# Power.net
KiCad netlist of a schematic drawn in Altium Designer
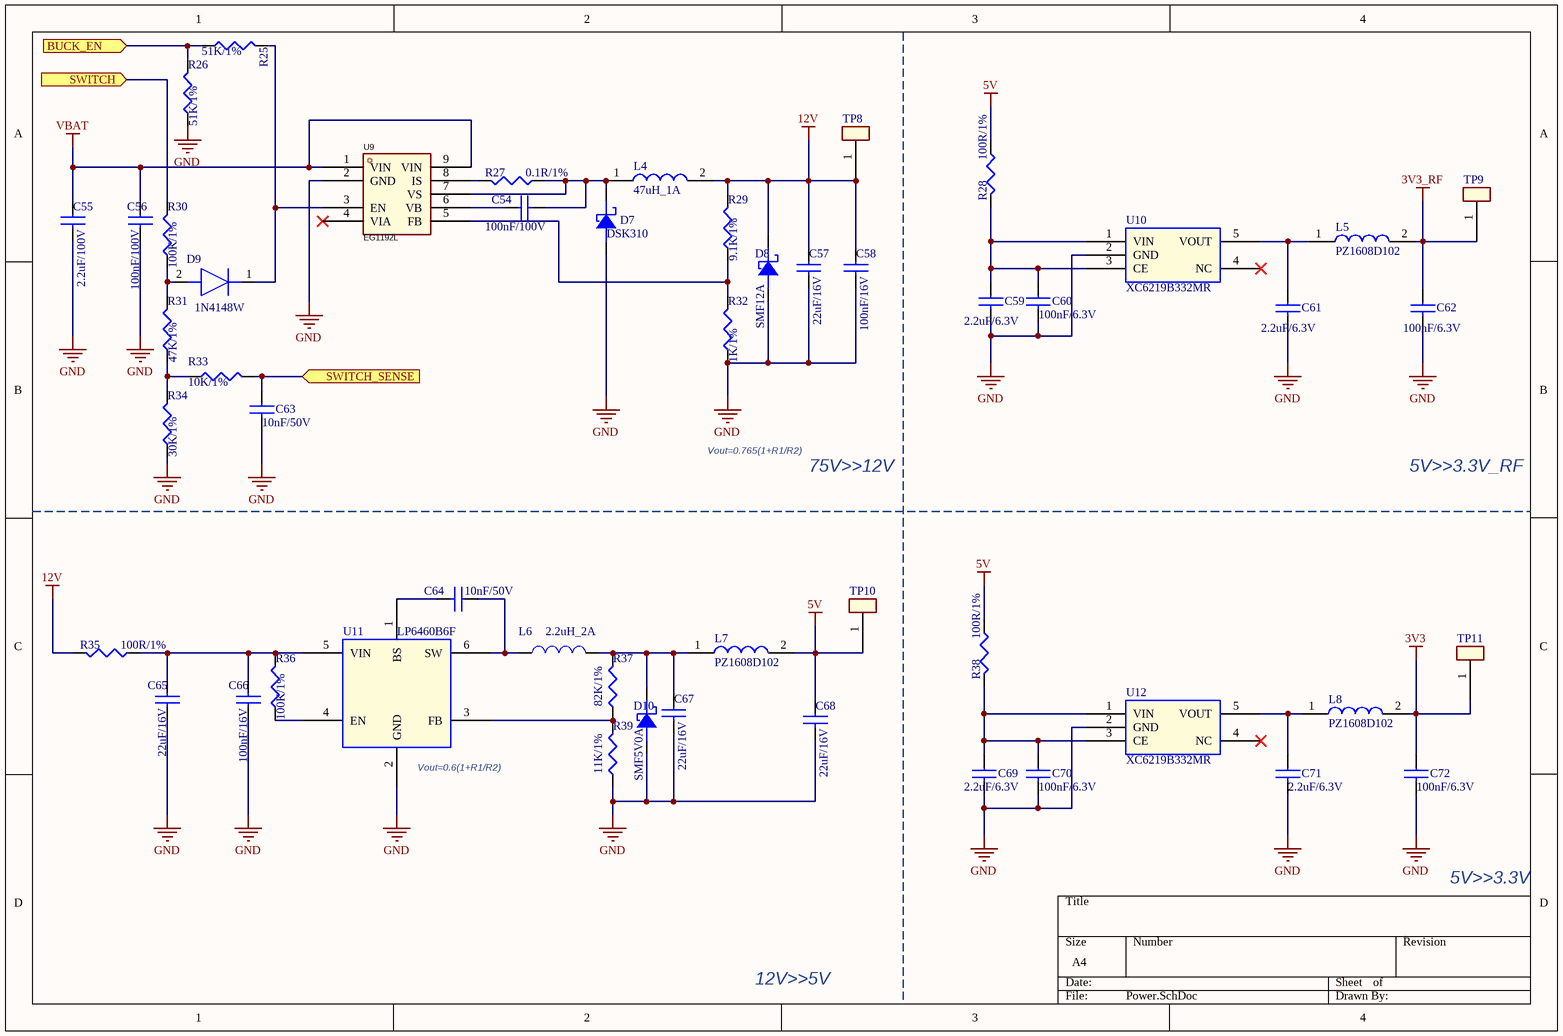
[diagram p0: Power.SchDoc]

(export (version "E")
  (design (tool "Eeschema 10.0.6"))
  (components
    (comp (ref "C54") (value "100nF/100V") (footprint "C0603") (libsource (lib "*") (part "CAP NP")))
    (comp (ref "C55") (value "2.2uF/100V") (footprint "C1206") (libsource (lib "*") (part "CAP NP")))
    (comp (ref "C56") (value "100nF/100V") (footprint "C0603") (libsource (lib "*") (part "CAP NP")))
    (comp (ref "C57") (value "22uF/16V") (footprint "C0805") (libsource (lib "*") (part "CAP NP")))
    (comp (ref "C58") (value "100nF/16V") (footprint "C0805") (libsource (lib "*") (part "CAP NP")))
    (comp (ref "C59") (value "2.2uF/6.3V") (footprint "C0402") (libsource (lib "*") (part "CAP NP")))
    (comp (ref "C60") (value "100nF/6.3V") (footprint "C0402") (libsource (lib "*") (part "CAP NP")))
    (comp (ref "C61") (value "2.2uF/6.3V") (footprint "C0402") (libsource (lib "*") (part "CAP NP")))
    (comp (ref "C62") (value "100nF/6.3V") (footprint "C0402") (libsource (lib "*") (part "CAP NP")))
    (comp (ref "C63") (value "10nF/50V") (footprint "C0402") (libsource (lib "*") (part "CAP NP")))
    (comp (ref "C64") (value "10nF/50V") (footprint "C0402") (libsource (lib "*") (part "CAP NP")))
    (comp (ref "C65") (value "22uF/16V") (footprint "C0805") (libsource (lib "*") (part "CAP NP")))
    (comp (ref "C66") (value "100nF/16V") (footprint "C0805") (libsource (lib "*") (part "CAP NP")))
    (comp (ref "C67") (value "22uF/16V") (footprint "C0805") (libsource (lib "*") (part "CAP NP")))
    (comp (ref "C68") (value "22uF/16V") (footprint "C0805") (libsource (lib "*") (part "CAP NP")))
    (comp (ref "C69") (value "2.2uF/6.3V") (footprint "C0402") (libsource (lib "*") (part "CAP NP")))
    (comp (ref "C70") (value "100nF/6.3V") (footprint "C0402") (libsource (lib "*") (part "CAP NP")))
    (comp (ref "C71") (value "2.2uF/6.3V") (footprint "C0402") (libsource (lib "*") (part "CAP NP")))
    (comp (ref "C72") (value "100nF/6.3V") (footprint "C0402") (libsource (lib "*") (part "CAP NP")))
    (comp (ref "D7") (value "DSK310") (footprint "SOD-123F") (libsource (lib "*") (part "DIODE SCHOTTKY21")))
    (comp (ref "D8") (value "SMF12A") (footprint "SOD-123F") (libsource (lib "*") (part "DIODE SCHOTTKY21")))
    (comp (ref "D9")
      (value "1N4148W")
      (footprint "1N4148WVGS08")
      (description "Diode")
      (fields
        (field (name "MANUFACTURER_PART_NUMBER") "1N4148W-V-GS08")
        (field (name "MOUSER PART NUMBER") "625-1N4148W-V")
      )
      (libsource (lib "VESC_DEVICE_Library") (part "1N4148W-V-GS08"))
    )
    (comp (ref "D10")
      (value "SMF5V0A")
      (footprint "SOD-123F")
      (libsource (lib "*") (part "DIODE SCHOTTKY21"))
    )
    (comp (ref "L4")
      (value "47uH_1A")
      (footprint "L5040")
      (description "Inductor")
      (fields
        (field (name "MANUFACTURER_PART_NUMBER") "74404054221")
        (field (name "MOUSER PART NUMBER") "710-74404054221")
      )
      (libsource (lib "VESC_DEVICE_Library") (part "74404054221"))
    )
    (comp (ref "L5")
      (value "PZ1608D102")
      (footprint "L0603")
      (description "Inductor")
      (fields
        (field (name "MANUFACTURER_PART_NUMBER") "LQG15HS4N7C02D")
        (field (name "MOUSER PART NUMBER") "81-LQG15HS4N7C02D")
      )
      (libsource (lib "VESC_DEVICE_Library") (part "PZ1608D102"))
    )
    (comp (ref "L6") (value "2.2uH_2A") (footprint "L4020") (libsource (lib "*") (part "INDUCTOR")))
    (comp (ref "L7")
      (value "PZ1608D102")
      (footprint "L0603")
      (description "Inductor")
      (fields
        (field (name "MANUFACTURER_PART_NUMBER") "LQG15HS4N7C02D")
        (field (name "MOUSER PART NUMBER") "81-LQG15HS4N7C02D")
      )
      (libsource (lib "VESC_DEVICE_Library") (part "PZ1608D102"))
    )
    (comp (ref "L8")
      (value "PZ1608D102")
      (footprint "L0603")
      (description "Inductor")
      (fields
        (field (name "MANUFACTURER_PART_NUMBER") "LQG15HS4N7C02D")
        (field (name "MOUSER PART NUMBER") "81-LQG15HS4N7C02D")
      )
      (libsource (lib "VESC_DEVICE_Library") (part "PZ1608D102"))
    )
    (comp (ref "R25") (value "51K/1%") (footprint "R0402") (libsource (lib "*") (part "RESISTOR")))
    (comp (ref "R26") (value "51K/1%") (footprint "R0402") (libsource (lib "*") (part "RESISTOR")))
    (comp (ref "R27") (value "0.1R/1%") (footprint "R0603") (libsource (lib "*") (part "RESISTOR")))
    (comp (ref "R28") (value "100R/1%") (footprint "R0603") (libsource (lib "*") (part "RESISTOR")))
    (comp (ref "R29") (value "9.1K/1%") (footprint "R0402") (libsource (lib "*") (part "RESISTOR")))
    (comp (ref "R30") (value "100K/1%") (footprint "R0402") (libsource (lib "*") (part "RESISTOR")))
    (comp (ref "R31") (value "47K/1%") (footprint "R0402") (libsource (lib "*") (part "RESISTOR")))
    (comp (ref "R32") (value "1K/1%") (footprint "R0402") (libsource (lib "*") (part "RESISTOR")))
    (comp (ref "R33") (value "10K/1%") (footprint "R0402") (libsource (lib "*") (part "RESISTOR")))
    (comp (ref "R34") (value "30K/1%") (footprint "R0402") (libsource (lib "*") (part "RESISTOR")))
    (comp (ref "R35") (value "100R/1%") (footprint "R0603") (libsource (lib "*") (part "RESISTOR")))
    (comp (ref "R36") (value "100K/1%") (footprint "R0402") (libsource (lib "*") (part "RESISTOR")))
    (comp (ref "R37") (value "82K/1%") (footprint "R0402") (libsource (lib "*") (part "RESISTOR")))
    (comp (ref "R38") (value "100R/1%") (footprint "R0603") (libsource (lib "*") (part "RESISTOR")))
    (comp (ref "R39") (value "11K/1%") (footprint "R0402") (libsource (lib "*") (part "RESISTOR")))
    (comp (ref "TP8")
      (value "TEST POINT")
      (footprint "test_point_100_smd")
      (libsource (lib "VESC_DEVICE_Library") (part "TEST POINT"))
    )
    (comp (ref "TP9")
      (value "TEST POINT")
      (footprint "test_point_100_smd")
      (libsource (lib "VESC_DEVICE_Library") (part "TEST POINT"))
    )
    (comp (ref "TP10")
      (value "TEST POINT")
      (footprint "test_point_100_smd")
      (libsource (lib "VESC_DEVICE_Library") (part "TEST POINT"))
    )
    (comp (ref "TP11")
      (value "TEST POINT")
      (footprint "test_point_100_smd")
      (libsource (lib "VESC_DEVICE_Library") (part "TEST POINT"))
    )
    (comp (ref "U9")
      (value "EG1192L")
      (footprint "ESOP-8_L4.9-W3.9-P1.27-LS6.0-BL-EP-1")
      (fields (field (name "MANUFACTURER") "EG(屹晶微)") (field (name "MANUFACTURER PART") "EG1198"))
      (libsource (lib "VESC_DEVICE_Library") (part "EG1192L"))
    )
    (comp (ref "U10")
      (value "XC6219B332MR")
      (footprint "SOT-23-5")
      (libsource (lib "*") (part "XC6219B332MR"))
    )
    (comp (ref "U11") (value "LP6460B6F") (footprint "SOT-23-6") (libsource (lib "*") (part "LP6460B6F")))
    (comp (ref "U12")
      (value "XC6219B332MR")
      (footprint "SOT-23-5")
      (libsource (lib "*") (part "XC6219B332MR"))
    )
  )
  (nets
    (net (code "1") (name "/BUCK_EN") (class "Default")
      (node (ref "R25") (pin "1") (pinfunction "1_1") (pintype "passive"))
      (node (ref "R26") (pin "2") (pinfunction "2_2") (pintype "passive"))
    )
    (net (code "2") (name "/SWITCH") (class "Default")
      (node (ref "R30") (pin "2") (pinfunction "2_2") (pintype "passive"))
    )
    (net (code "3") (name "/SWITCH_SENSE") (class "Default")
      (node (ref "C63") (pin "1") (pinfunction "1_1") (pintype "passive"))
      (node (ref "R33") (pin "2") (pinfunction "2_2") (pintype "passive"))
    )
    (net (code "4") (name "3V3") (class "Default")
      (node (ref "C72") (pin "1") (pinfunction "1_1") (pintype "passive"))
      (node (ref "L8") (pin "2") (pinfunction "2_2") (pintype "passive"))
      (node (ref "TP11") (pin "1") (pinfunction "1_1") (pintype "passive"))
    )
    (net (code "5") (name "3V3_RF") (class "Default")
      (node (ref "C62") (pin "1") (pinfunction "1_1") (pintype "passive"))
      (node (ref "L5") (pin "2") (pinfunction "2_2") (pintype "passive"))
      (node (ref "TP9") (pin "1") (pinfunction "1_1") (pintype "passive"))
    )
    (net (code "6") (name "5V") (class "Default")
      (node (ref "C68") (pin "1") (pinfunction "1_1") (pintype "passive"))
      (node (ref "L7") (pin "2") (pinfunction "2_2") (pintype "passive"))
      (node (ref "R28") (pin "1") (pinfunction "1_1") (pintype "passive"))
      (node (ref "R38") (pin "1") (pinfunction "1_1") (pintype "passive"))
      (node (ref "TP10") (pin "1") (pinfunction "1_1") (pintype "passive"))
    )
    (net (code "7") (name "12V") (class "Default")
      (node (ref "C57") (pin "1") (pinfunction "1_1") (pintype "passive"))
      (node (ref "C58") (pin "1") (pinfunction "1_1") (pintype "passive"))
      (node (ref "D8") (pin "1") (pinfunction "K_1") (pintype "passive"))
      (node (ref "L4") (pin "2") (pinfunction "2_2") (pintype "passive"))
      (node (ref "R29") (pin "2") (pinfunction "2_2") (pintype "passive"))
      (node (ref "R35") (pin "2") (pinfunction "2_2") (pintype "passive"))
      (node (ref "TP8") (pin "1") (pinfunction "1_1") (pintype "passive"))
    )
    (net (code "8") (name "GND") (class "Default")
      (node (ref "C55") (pin "2") (pinfunction "2_2") (pintype "passive"))
      (node (ref "C56") (pin "2") (pinfunction "2_2") (pintype "passive"))
      (node (ref "C57") (pin "2") (pinfunction "2_2") (pintype "passive"))
      (node (ref "C58") (pin "2") (pinfunction "2_2") (pintype "passive"))
      (node (ref "C59") (pin "2") (pinfunction "2_2") (pintype "passive"))
      (node (ref "C60") (pin "2") (pinfunction "2_2") (pintype "passive"))
      (node (ref "C61") (pin "2") (pinfunction "2_2") (pintype "passive"))
      (node (ref "C62") (pin "2") (pinfunction "2_2") (pintype "passive"))
      (node (ref "C63") (pin "2") (pinfunction "2_2") (pintype "passive"))
      (node (ref "C65") (pin "2") (pinfunction "2_2") (pintype "passive"))
      (node (ref "C66") (pin "2") (pinfunction "2_2") (pintype "passive"))
      (node (ref "C67") (pin "2") (pinfunction "2_2") (pintype "passive"))
      (node (ref "C68") (pin "2") (pinfunction "2_2") (pintype "passive"))
      (node (ref "C69") (pin "2") (pinfunction "2_2") (pintype "passive"))
      (node (ref "C70") (pin "2") (pinfunction "2_2") (pintype "passive"))
      (node (ref "C71") (pin "2") (pinfunction "2_2") (pintype "passive"))
      (node (ref "C72") (pin "2") (pinfunction "2_2") (pintype "passive"))
      (node (ref "D10") (pin "2") (pinfunction "A_2") (pintype "passive"))
      (node (ref "D7") (pin "2") (pinfunction "A_2") (pintype "passive"))
      (node (ref "D8") (pin "2") (pinfunction "A_2") (pintype "passive"))
      (node (ref "R26") (pin "1") (pinfunction "1_1") (pintype "passive"))
      (node (ref "R32") (pin "1") (pinfunction "1_1") (pintype "passive"))
      (node (ref "R34") (pin "1") (pinfunction "1_1") (pintype "passive"))
      (node (ref "R39") (pin "1") (pinfunction "1_1") (pintype "passive"))
      (node (ref "U10") (pin "2") (pinfunction "GND_2") (pintype "passive"))
      (node (ref "U11") (pin "2") (pinfunction "GND_2") (pintype "passive"))
      (node (ref "U12") (pin "2") (pinfunction "GND_2") (pintype "passive"))
      (node (ref "U9") (pin "2") (pinfunction "GND_2") (pintype "passive"))
    )
    (net (code "9") (name "Net-(D7-K)") (class "Default")
      (node (ref "C54") (pin "2") (pinfunction "2_2") (pintype "passive"))
      (node (ref "D7") (pin "1") (pinfunction "K_1") (pintype "passive"))
      (node (ref "L4") (pin "1") (pinfunction "1_1") (pintype "passive"))
      (node (ref "R27") (pin "1") (pinfunction "1_1") (pintype "passive"))
      (node (ref "U9") (pin "7") (pinfunction "VS_7") (pintype "passive"))
    )
    (net (code "10") (name "Net-(D9-A)") (class "Default")
      (node (ref "D9") (pin "2") (pinfunction "A_2") (pintype "passive"))
      (node (ref "R30") (pin "1") (pinfunction "1_1") (pintype "passive"))
      (node (ref "R31") (pin "2") (pinfunction "2_2") (pintype "passive"))
    )
    (net (code "11") (name "Net-(D9-K)") (class "Default")
      (node (ref "D9") (pin "1") (pinfunction "K_1") (pintype "passive"))
      (node (ref "R25") (pin "2") (pinfunction "2_2") (pintype "passive"))
      (node (ref "U9") (pin "3") (pinfunction "EN_3") (pintype "passive"))
    )
    (net (code "12") (name "Net-(D10-K)") (class "Default")
      (node (ref "C67") (pin "1") (pinfunction "1_1") (pintype "passive"))
      (node (ref "D10") (pin "1") (pinfunction "K_1") (pintype "passive"))
      (node (ref "L6") (pin "2") (pinfunction "2_2") (pintype "passive"))
      (node (ref "L7") (pin "1") (pinfunction "1_1") (pintype "passive"))
      (node (ref "R37") (pin "2") (pinfunction "2_2") (pintype "passive"))
    )
    (net (code "13") (name "Net-(R31-Pad1)") (class "Default")
      (node (ref "R31") (pin "1") (pinfunction "1_1") (pintype "passive"))
      (node (ref "R33") (pin "1") (pinfunction "1_1") (pintype "passive"))
      (node (ref "R34") (pin "2") (pinfunction "2_2") (pintype "passive"))
    )
    (net (code "14") (name "Net-(U9-FB)") (class "Default")
      (node (ref "R29") (pin "1") (pinfunction "1_1") (pintype "passive"))
      (node (ref "R32") (pin "2") (pinfunction "2_2") (pintype "passive"))
      (node (ref "U9") (pin "5") (pinfunction "FB_5") (pintype "passive"))
    )
    (net (code "15") (name "Net-(U9-IS)") (class "Default")
      (node (ref "R27") (pin "2") (pinfunction "2_2") (pintype "passive"))
      (node (ref "U9") (pin "8") (pinfunction "IS_8") (pintype "passive"))
    )
    (net (code "16") (name "Net-(U9-VB)") (class "Default")
      (node (ref "C54") (pin "1") (pinfunction "1_1") (pintype "passive"))
      (node (ref "U9") (pin "6") (pinfunction "VB_6") (pintype "passive"))
    )
    (net (code "17") (name "Net-(U10-CE)") (class "Default")
      (node (ref "C59") (pin "1") (pinfunction "1_1") (pintype "passive"))
      (node (ref "C60") (pin "1") (pinfunction "1_1") (pintype "passive"))
      (node (ref "R28") (pin "2") (pinfunction "2_2") (pintype "passive"))
      (node (ref "U10") (pin "1") (pinfunction "VIN_1") (pintype "passive"))
      (node (ref "U10") (pin "3") (pinfunction "CE_3") (pintype "passive"))
    )
    (net (code "18") (name "Net-(U10-VOUT)") (class "Default")
      (node (ref "C61") (pin "1") (pinfunction "1_1") (pintype "passive"))
      (node (ref "L5") (pin "1") (pinfunction "1_1") (pintype "passive"))
      (node (ref "U10") (pin "5") (pinfunction "VOUT_5") (pintype "passive"))
    )
    (net (code "19") (name "Net-(U11-BS)") (class "Default")
      (node (ref "C64") (pin "2") (pinfunction "2_2") (pintype "passive"))
      (node (ref "U11") (pin "1") (pinfunction "BS_1") (pintype "passive"))
    )
    (net (code "20") (name "Net-(U11-EN)") (class "Default")
      (node (ref "R36") (pin "1") (pinfunction "1_1") (pintype "passive"))
      (node (ref "U11") (pin "4") (pinfunction "EN_4") (pintype "passive"))
    )
    (net (code "21") (name "Net-(U11-FB)") (class "Default")
      (node (ref "R37") (pin "1") (pinfunction "1_1") (pintype "passive"))
      (node (ref "R39") (pin "2") (pinfunction "2_2") (pintype "passive"))
      (node (ref "U11") (pin "3") (pinfunction "FB_3") (pintype "passive"))
    )
    (net (code "22") (name "Net-(U11-SW)") (class "Default")
      (node (ref "C64") (pin "1") (pinfunction "1_1") (pintype "passive"))
      (node (ref "L6") (pin "1") (pinfunction "1_1") (pintype "passive"))
      (node (ref "U11") (pin "6") (pinfunction "SW_6") (pintype "passive"))
    )
    (net (code "23") (name "Net-(U11-VIN)") (class "Default")
      (node (ref "C65") (pin "1") (pinfunction "1_1") (pintype "passive"))
      (node (ref "C66") (pin "1") (pinfunction "1_1") (pintype "passive"))
      (node (ref "R35") (pin "1") (pinfunction "1_1") (pintype "passive"))
      (node (ref "R36") (pin "2") (pinfunction "2_2") (pintype "passive"))
      (node (ref "U11") (pin "5") (pinfunction "VIN_5") (pintype "passive"))
    )
    (net (code "24") (name "Net-(U12-CE)") (class "Default")
      (node (ref "C69") (pin "1") (pinfunction "1_1") (pintype "passive"))
      (node (ref "C70") (pin "1") (pinfunction "1_1") (pintype "passive"))
      (node (ref "R38") (pin "2") (pinfunction "2_2") (pintype "passive"))
      (node (ref "U12") (pin "1") (pinfunction "VIN_1") (pintype "passive"))
      (node (ref "U12") (pin "3") (pinfunction "CE_3") (pintype "passive"))
    )
    (net (code "25") (name "Net-(U12-VOUT)") (class "Default")
      (node (ref "C71") (pin "1") (pinfunction "1_1") (pintype "passive"))
      (node (ref "L8") (pin "1") (pinfunction "1_1") (pintype "passive"))
      (node (ref "U12") (pin "5") (pinfunction "VOUT_5") (pintype "passive"))
    )
    (net (code "26") (name "VBAT") (class "Default")
      (node (ref "C55") (pin "1") (pinfunction "1_1") (pintype "passive"))
      (node (ref "C56") (pin "1") (pinfunction "1_1") (pintype "passive"))
      (node (ref "U9") (pin "1") (pinfunction "VIN_1") (pintype "passive"))
      (node (ref "U9") (pin "9") (pinfunction "VIN_9") (pintype "passive"))
    )
    (net (code "27") (name "unconnected-(U9-VIA-Pad4)") (class "Default")
      (node (ref "U9") (pin "4") (pinfunction "VIA_4") (pintype "passive+no_connect"))
    )
    (net (code "28") (name "unconnected-(U10-NC-Pad4)") (class "Default")
      (node (ref "U10") (pin "4") (pinfunction "NC_4") (pintype "passive+no_connect"))
    )
    (net (code "29") (name "unconnected-(U12-NC-Pad4)") (class "Default")
      (node (ref "U12") (pin "4") (pinfunction "NC_4") (pintype "passive+no_connect"))
    )
  )
)
